# Top_Board.net
KiCad netlist of a schematic drawn in EAGLE
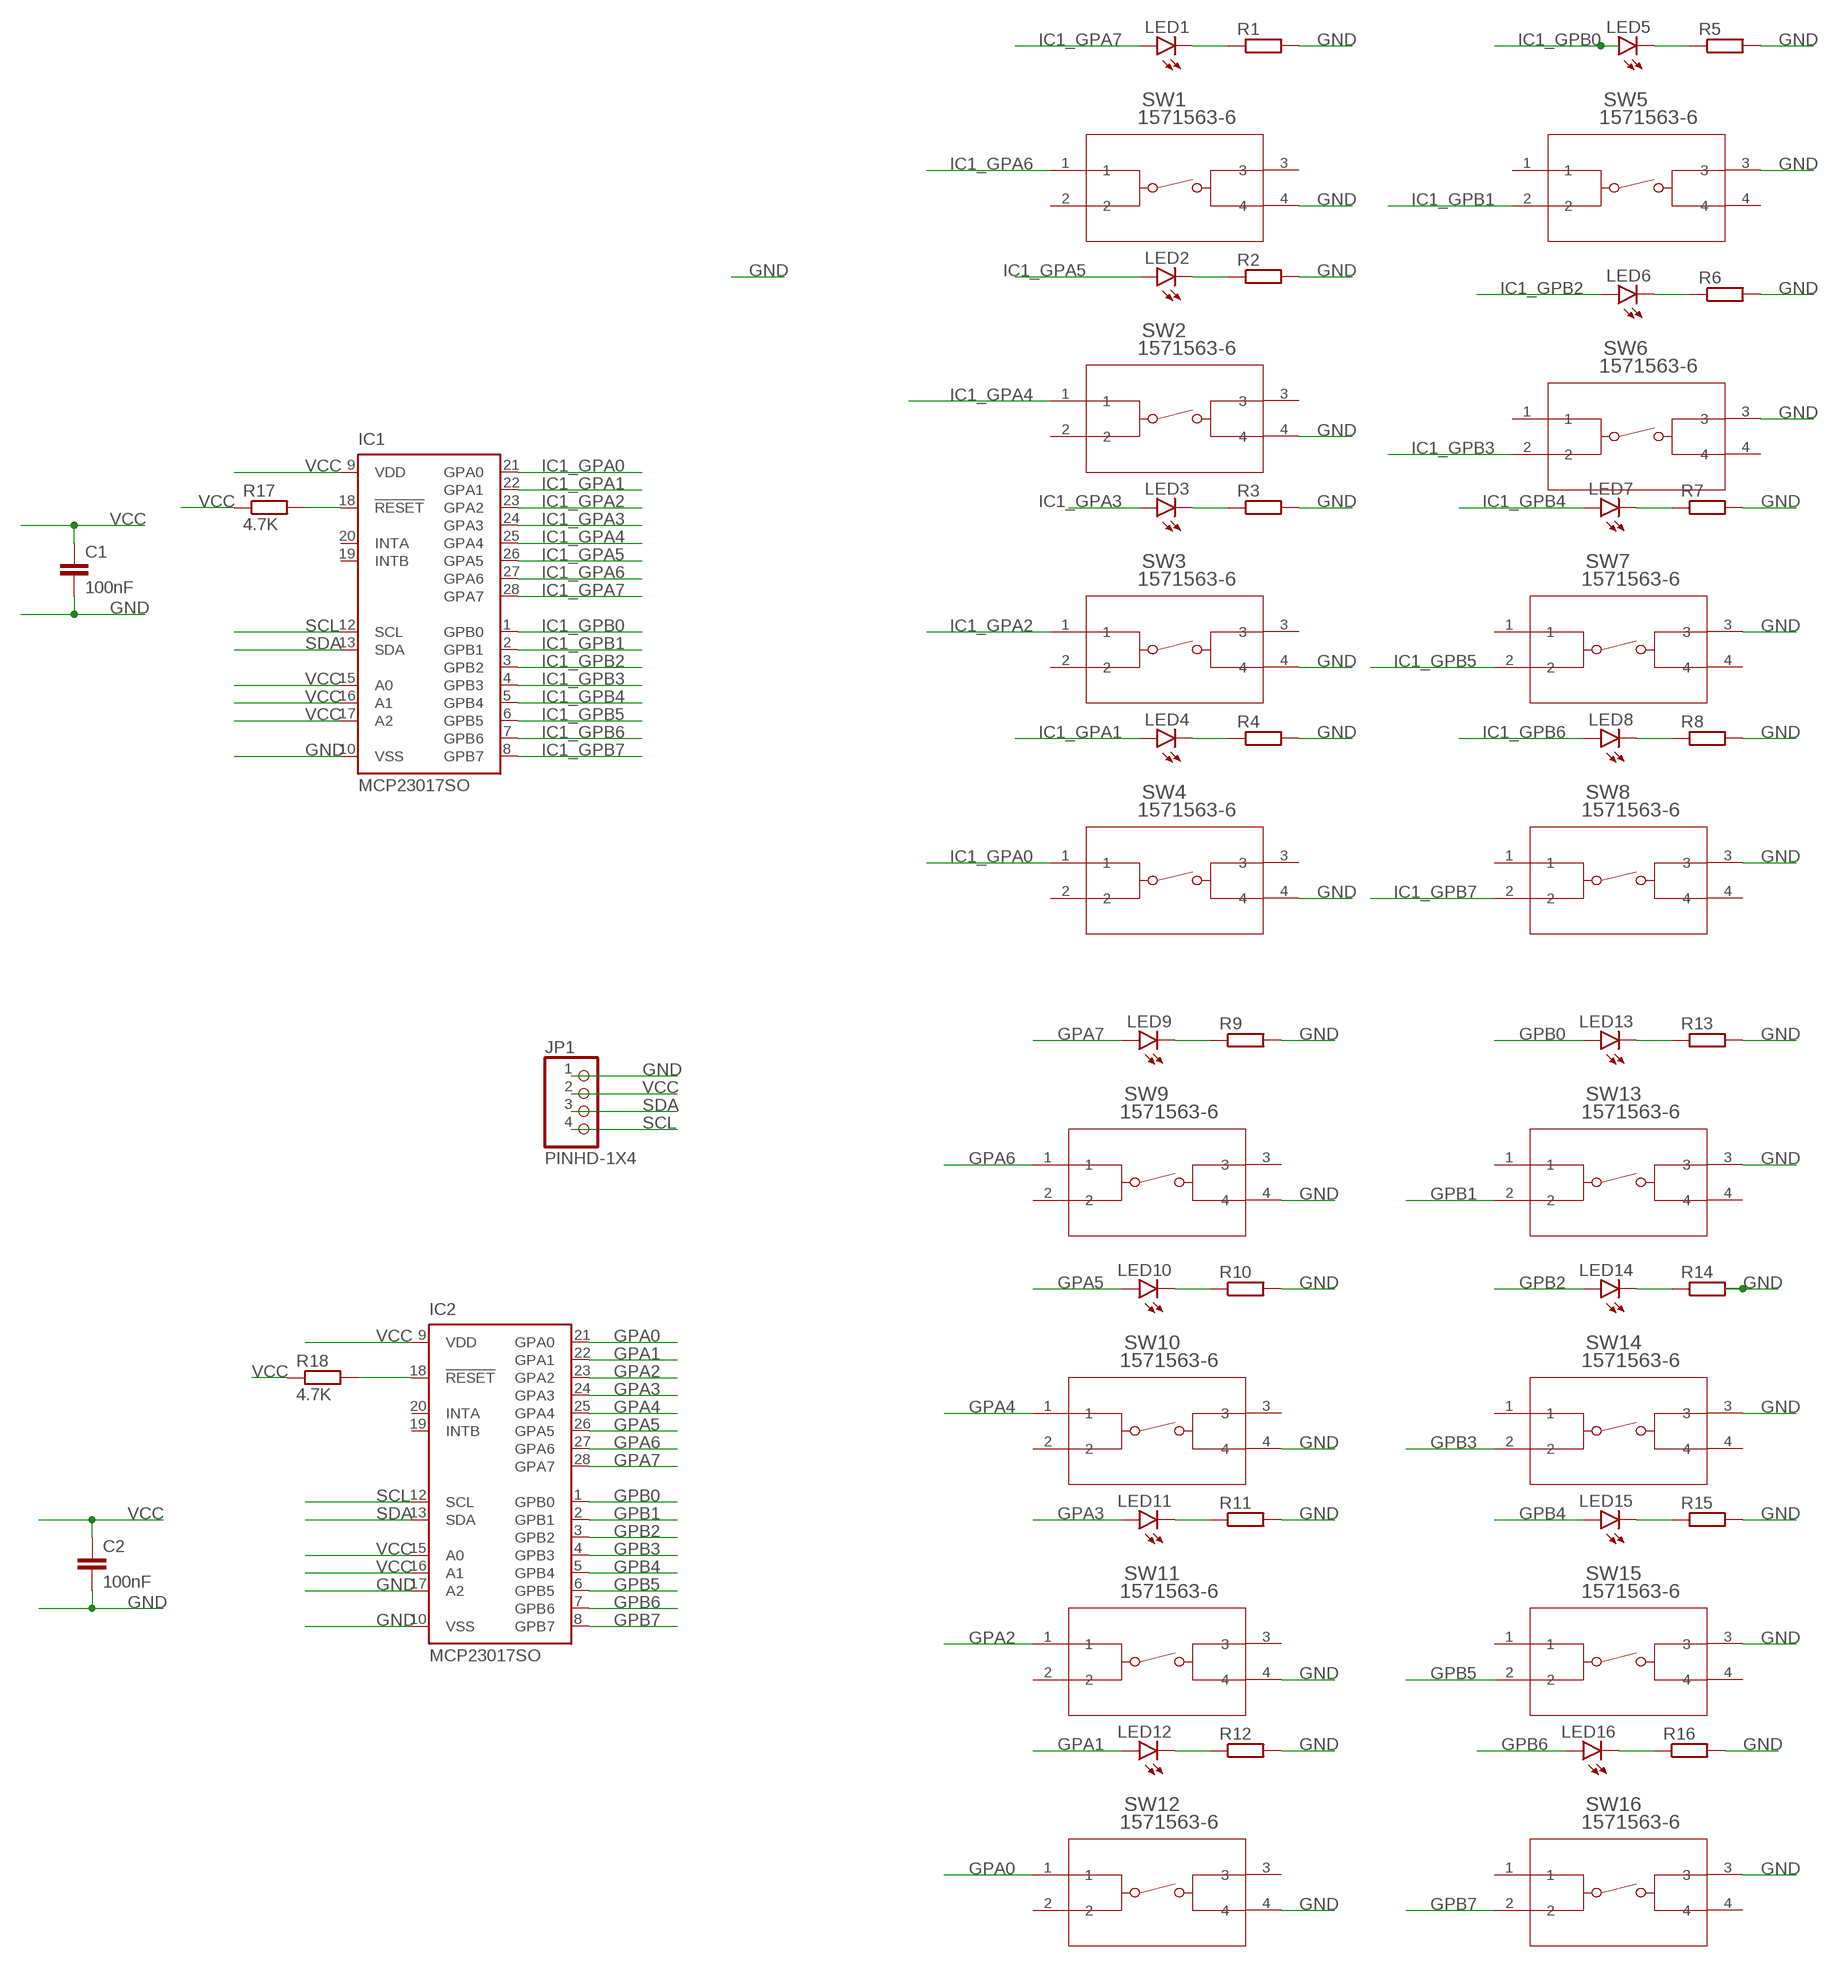
[diagram p0: schematic, sheet 1]

(export (version "E")
  (design (tool "Eeschema 10.0.6"))
  (components
    (comp (ref "C1")
      (value "100nF")
      (footprint "eagle-import:C025-025X050")
      (libsource (lib "eagle-import") (part "C-EU025-025X050"))
    )
    (comp (ref "C2")
      (value "100nF")
      (footprint "eagle-import:C025-025X050")
      (libsource (lib "eagle-import") (part "C-EU025-025X050"))
    )
    (comp (ref "IC1")
      (value "MCP23017SO")
      (footprint "eagle-import:SO28W")
      (fields (field (name "MF") "MICROCHIP") (field (name "MPN") "MCP23017-E/SO"))
      (libsource (lib "eagle-import") (part "MCP23017SO"))
    )
    (comp (ref "IC2")
      (value "MCP23017SO")
      (footprint "eagle-import:SO28W")
      (fields (field (name "MF") "MICROCHIP") (field (name "MPN") "MCP23017-E/SO"))
      (libsource (lib "eagle-import") (part "MCP23017SO"))
    )
    (comp (ref "JP1")
      (value "PINHD-1X4")
      (footprint "eagle-import:1X04")
      (libsource (lib "eagle-import") (part "PINHD-1X4"))
    )
    (comp (ref "LED1")
      (value "LEDCHIP-LED0805")
      (footprint "eagle-import:CHIP-LED0805")
      (libsource (lib "eagle-import") (part "LEDCHIP-LED0805"))
    )
    (comp (ref "LED2")
      (value "LEDCHIP-LED0805")
      (footprint "eagle-import:CHIP-LED0805")
      (libsource (lib "eagle-import") (part "LEDCHIP-LED0805"))
    )
    (comp (ref "LED3")
      (value "LEDCHIP-LED0805")
      (footprint "eagle-import:CHIP-LED0805")
      (libsource (lib "eagle-import") (part "LEDCHIP-LED0805"))
    )
    (comp (ref "LED4")
      (value "LEDCHIP-LED0805")
      (footprint "eagle-import:CHIP-LED0805")
      (libsource (lib "eagle-import") (part "LEDCHIP-LED0805"))
    )
    (comp (ref "LED5")
      (value "LEDCHIP-LED0805")
      (footprint "eagle-import:CHIP-LED0805")
      (libsource (lib "eagle-import") (part "LEDCHIP-LED0805"))
    )
    (comp (ref "LED6")
      (value "LEDCHIP-LED0805")
      (footprint "eagle-import:CHIP-LED0805")
      (libsource (lib "eagle-import") (part "LEDCHIP-LED0805"))
    )
    (comp (ref "LED7")
      (value "LEDCHIP-LED0805")
      (footprint "eagle-import:CHIP-LED0805")
      (libsource (lib "eagle-import") (part "LEDCHIP-LED0805"))
    )
    (comp (ref "LED8")
      (value "LEDCHIP-LED0805")
      (footprint "eagle-import:CHIP-LED0805")
      (libsource (lib "eagle-import") (part "LEDCHIP-LED0805"))
    )
    (comp (ref "LED9")
      (value "LEDCHIP-LED0805")
      (footprint "eagle-import:CHIP-LED0805")
      (libsource (lib "eagle-import") (part "LEDCHIP-LED0805"))
    )
    (comp (ref "LED10")
      (value "LEDCHIP-LED0805")
      (footprint "eagle-import:CHIP-LED0805")
      (libsource (lib "eagle-import") (part "LEDCHIP-LED0805"))
    )
    (comp (ref "LED11")
      (value "LEDCHIP-LED0805")
      (footprint "eagle-import:CHIP-LED0805")
      (libsource (lib "eagle-import") (part "LEDCHIP-LED0805"))
    )
    (comp (ref "LED12")
      (value "LEDCHIP-LED0805")
      (footprint "eagle-import:CHIP-LED0805")
      (libsource (lib "eagle-import") (part "LEDCHIP-LED0805"))
    )
    (comp (ref "LED13")
      (value "LEDCHIP-LED0805")
      (footprint "eagle-import:CHIP-LED0805")
      (libsource (lib "eagle-import") (part "LEDCHIP-LED0805"))
    )
    (comp (ref "LED14")
      (value "LEDCHIP-LED0805")
      (footprint "eagle-import:CHIP-LED0805")
      (libsource (lib "eagle-import") (part "LEDCHIP-LED0805"))
    )
    (comp (ref "LED15")
      (value "LEDCHIP-LED0805")
      (footprint "eagle-import:CHIP-LED0805")
      (libsource (lib "eagle-import") (part "LEDCHIP-LED0805"))
    )
    (comp (ref "LED16")
      (value "LEDCHIP-LED0805")
      (footprint "eagle-import:CHIP-LED0805")
      (libsource (lib "eagle-import") (part "LEDCHIP-LED0805"))
    )
    (comp (ref "R1")
      (value "R-EU_R0805")
      (footprint "eagle-import:R0805")
      (libsource (lib "eagle-import") (part "R-EU_R0805"))
    )
    (comp (ref "R2")
      (value "R-EU_R0805")
      (footprint "eagle-import:R0805")
      (libsource (lib "eagle-import") (part "R-EU_R0805"))
    )
    (comp (ref "R3")
      (value "R-EU_R0805")
      (footprint "eagle-import:R0805")
      (libsource (lib "eagle-import") (part "R-EU_R0805"))
    )
    (comp (ref "R4")
      (value "R-EU_R0805")
      (footprint "eagle-import:R0805")
      (libsource (lib "eagle-import") (part "R-EU_R0805"))
    )
    (comp (ref "R5")
      (value "R-EU_R0805")
      (footprint "eagle-import:R0805")
      (libsource (lib "eagle-import") (part "R-EU_R0805"))
    )
    (comp (ref "R6")
      (value "R-EU_R0805")
      (footprint "eagle-import:R0805")
      (libsource (lib "eagle-import") (part "R-EU_R0805"))
    )
    (comp (ref "R7")
      (value "R-EU_R0805")
      (footprint "eagle-import:R0805")
      (libsource (lib "eagle-import") (part "R-EU_R0805"))
    )
    (comp (ref "R8")
      (value "R-EU_R0805")
      (footprint "eagle-import:R0805")
      (libsource (lib "eagle-import") (part "R-EU_R0805"))
    )
    (comp (ref "R9")
      (value "R-EU_R0805")
      (footprint "eagle-import:R0805")
      (libsource (lib "eagle-import") (part "R-EU_R0805"))
    )
    (comp (ref "R10")
      (value "R-EU_R0805")
      (footprint "eagle-import:R0805")
      (libsource (lib "eagle-import") (part "R-EU_R0805"))
    )
    (comp (ref "R11")
      (value "R-EU_R0805")
      (footprint "eagle-import:R0805")
      (libsource (lib "eagle-import") (part "R-EU_R0805"))
    )
    (comp (ref "R12")
      (value "R-EU_R0805")
      (footprint "eagle-import:R0805")
      (libsource (lib "eagle-import") (part "R-EU_R0805"))
    )
    (comp (ref "R13")
      (value "R-EU_R0805")
      (footprint "eagle-import:R0805")
      (libsource (lib "eagle-import") (part "R-EU_R0805"))
    )
    (comp (ref "R14")
      (value "R-EU_R0805")
      (footprint "eagle-import:R0805")
      (libsource (lib "eagle-import") (part "R-EU_R0805"))
    )
    (comp (ref "R15")
      (value "R-EU_R0805")
      (footprint "eagle-import:R0805")
      (libsource (lib "eagle-import") (part "R-EU_R0805"))
    )
    (comp (ref "R16")
      (value "R-EU_R0805")
      (footprint "eagle-import:R0805")
      (libsource (lib "eagle-import") (part "R-EU_R0805"))
    )
    (comp (ref "R17")
      (value "4.7K")
      (footprint "eagle-import:R0805")
      (libsource (lib "eagle-import") (part "R-EU_R0805"))
    )
    (comp (ref "R18")
      (value "4.7K")
      (footprint "eagle-import:R0805")
      (libsource (lib "eagle-import") (part "R-EU_R0805"))
    )
    (comp (ref "SW1")
      (value "1571563-6")
      (footprint "eagle-import:SW4_1437565-E")
      (fields (field (name "COPYRIGHT") "Copyright (C) 2016 Accelerated Designs. All rights reserved"))
      (libsource (lib "eagle-import") (part "1571563-6"))
    )
    (comp (ref "SW2")
      (value "1571563-6")
      (footprint "eagle-import:SW4_1437565-E")
      (fields (field (name "COPYRIGHT") "Copyright (C) 2016 Accelerated Designs. All rights reserved"))
      (libsource (lib "eagle-import") (part "1571563-6"))
    )
    (comp (ref "SW3")
      (value "1571563-6")
      (footprint "eagle-import:SW4_1437565-E")
      (fields (field (name "COPYRIGHT") "Copyright (C) 2016 Accelerated Designs. All rights reserved"))
      (libsource (lib "eagle-import") (part "1571563-6"))
    )
    (comp (ref "SW4")
      (value "1571563-6")
      (footprint "eagle-import:SW4_1437565-E")
      (fields (field (name "COPYRIGHT") "Copyright (C) 2016 Accelerated Designs. All rights reserved"))
      (libsource (lib "eagle-import") (part "1571563-6"))
    )
    (comp (ref "SW5")
      (value "1571563-6")
      (footprint "eagle-import:SW4_1437565-E")
      (fields (field (name "COPYRIGHT") "Copyright (C) 2016 Accelerated Designs. All rights reserved"))
      (libsource (lib "eagle-import") (part "1571563-6"))
    )
    (comp (ref "SW6")
      (value "1571563-6")
      (footprint "eagle-import:SW4_1437565-E")
      (fields (field (name "COPYRIGHT") "Copyright (C) 2016 Accelerated Designs. All rights reserved"))
      (libsource (lib "eagle-import") (part "1571563-6"))
    )
    (comp (ref "SW7")
      (value "1571563-6")
      (footprint "eagle-import:SW4_1437565-E")
      (fields (field (name "COPYRIGHT") "Copyright (C) 2016 Accelerated Designs. All rights reserved"))
      (libsource (lib "eagle-import") (part "1571563-6"))
    )
    (comp (ref "SW8")
      (value "1571563-6")
      (footprint "eagle-import:SW4_1437565-E")
      (fields (field (name "COPYRIGHT") "Copyright (C) 2016 Accelerated Designs. All rights reserved"))
      (libsource (lib "eagle-import") (part "1571563-6"))
    )
    (comp (ref "SW9")
      (value "1571563-6")
      (footprint "eagle-import:SW4_1437565-E")
      (fields (field (name "COPYRIGHT") "Copyright (C) 2016 Accelerated Designs. All rights reserved"))
      (libsource (lib "eagle-import") (part "1571563-6"))
    )
    (comp (ref "SW10")
      (value "1571563-6")
      (footprint "eagle-import:SW4_1437565-E")
      (fields (field (name "COPYRIGHT") "Copyright (C) 2016 Accelerated Designs. All rights reserved"))
      (libsource (lib "eagle-import") (part "1571563-6"))
    )
    (comp (ref "SW11")
      (value "1571563-6")
      (footprint "eagle-import:SW4_1437565-E")
      (fields (field (name "COPYRIGHT") "Copyright (C) 2016 Accelerated Designs. All rights reserved"))
      (libsource (lib "eagle-import") (part "1571563-6"))
    )
    (comp (ref "SW12")
      (value "1571563-6")
      (footprint "eagle-import:SW4_1437565-E")
      (fields (field (name "COPYRIGHT") "Copyright (C) 2016 Accelerated Designs. All rights reserved"))
      (libsource (lib "eagle-import") (part "1571563-6"))
    )
    (comp (ref "SW13")
      (value "1571563-6")
      (footprint "eagle-import:SW4_1437565-E")
      (fields (field (name "COPYRIGHT") "Copyright (C) 2016 Accelerated Designs. All rights reserved"))
      (libsource (lib "eagle-import") (part "1571563-6"))
    )
    (comp (ref "SW14")
      (value "1571563-6")
      (footprint "eagle-import:SW4_1437565-E")
      (fields (field (name "COPYRIGHT") "Copyright (C) 2016 Accelerated Designs. All rights reserved"))
      (libsource (lib "eagle-import") (part "1571563-6"))
    )
    (comp (ref "SW15")
      (value "1571563-6")
      (footprint "eagle-import:SW4_1437565-E")
      (fields (field (name "COPYRIGHT") "Copyright (C) 2016 Accelerated Designs. All rights reserved"))
      (libsource (lib "eagle-import") (part "1571563-6"))
    )
    (comp (ref "SW16")
      (value "1571563-6")
      (footprint "eagle-import:SW4_1437565-E")
      (fields (field (name "COPYRIGHT") "Copyright (C) 2016 Accelerated Designs. All rights reserved"))
      (libsource (lib "eagle-import") (part "1571563-6"))
    )
  )
  (nets
    (net (code "1") (name "/GND") (class "Default")
      (node (ref "C1") (pin "2") (pinfunction "2_2") (pintype "passive"))
      (node (ref "C2") (pin "2") (pinfunction "2_2") (pintype "passive"))
      (node (ref "IC1") (pin "10") (pinfunction "VSS_10") (pintype "power_in"))
      (node (ref "IC2") (pin "10") (pinfunction "VSS_10") (pintype "power_in"))
      (node (ref "IC2") (pin "17") (pinfunction "A2_17") (pintype "input"))
      (node (ref "JP1") (pin "1") (pinfunction "1_1") (pintype "passive"))
      (node (ref "R1") (pin "2") (pinfunction "2_2") (pintype "passive"))
      (node (ref "R10") (pin "2") (pinfunction "2_2") (pintype "passive"))
      (node (ref "R11") (pin "2") (pinfunction "2_2") (pintype "passive"))
      (node (ref "R12") (pin "2") (pinfunction "2_2") (pintype "passive"))
      (node (ref "R13") (pin "2") (pinfunction "2_2") (pintype "passive"))
      (node (ref "R14") (pin "2") (pinfunction "2_2") (pintype "passive"))
      (node (ref "R15") (pin "2") (pinfunction "2_2") (pintype "passive"))
      (node (ref "R16") (pin "2") (pinfunction "2_2") (pintype "passive"))
      (node (ref "R2") (pin "2") (pinfunction "2_2") (pintype "passive"))
      (node (ref "R3") (pin "2") (pinfunction "2_2") (pintype "passive"))
      (node (ref "R4") (pin "2") (pinfunction "2_2") (pintype "passive"))
      (node (ref "R5") (pin "2") (pinfunction "2_2") (pintype "passive"))
      (node (ref "R6") (pin "2") (pinfunction "2_2") (pintype "passive"))
      (node (ref "R7") (pin "2") (pinfunction "2_2") (pintype "passive"))
      (node (ref "R8") (pin "2") (pinfunction "2_2") (pintype "passive"))
      (node (ref "R9") (pin "2") (pinfunction "2_2") (pintype "passive"))
      (node (ref "SW1") (pin "4") (pinfunction "4_4") (pintype "passive"))
      (node (ref "SW10") (pin "4") (pinfunction "4_4") (pintype "passive"))
      (node (ref "SW11") (pin "4") (pinfunction "4_4") (pintype "passive"))
      (node (ref "SW12") (pin "4") (pinfunction "4_4") (pintype "passive"))
      (node (ref "SW13") (pin "3") (pinfunction "3_3") (pintype "passive"))
      (node (ref "SW14") (pin "3") (pinfunction "3_3") (pintype "passive"))
      (node (ref "SW15") (pin "3") (pinfunction "3_3") (pintype "passive"))
      (node (ref "SW16") (pin "3") (pinfunction "3_3") (pintype "passive"))
      (node (ref "SW2") (pin "4") (pinfunction "4_4") (pintype "passive"))
      (node (ref "SW3") (pin "4") (pinfunction "4_4") (pintype "passive"))
      (node (ref "SW4") (pin "4") (pinfunction "4_4") (pintype "passive"))
      (node (ref "SW5") (pin "3") (pinfunction "3_3") (pintype "passive"))
      (node (ref "SW6") (pin "3") (pinfunction "3_3") (pintype "passive"))
      (node (ref "SW7") (pin "3") (pinfunction "3_3") (pintype "passive"))
      (node (ref "SW8") (pin "3") (pinfunction "3_3") (pintype "passive"))
      (node (ref "SW9") (pin "4") (pinfunction "4_4") (pintype "passive"))
    )
    (net (code "2") (name "/GPA0") (class "Default")
      (node (ref "IC2") (pin "21") (pinfunction "GPA0_21") (pintype "bidirectional"))
      (node (ref "SW12") (pin "1") (pinfunction "1_1") (pintype "passive"))
    )
    (net (code "3") (name "/GPA1") (class "Default")
      (node (ref "IC2") (pin "22") (pinfunction "GPA1_22") (pintype "bidirectional"))
      (node (ref "LED12") (pin "A") (pinfunction "A_A") (pintype "passive"))
    )
    (net (code "4") (name "/GPA2") (class "Default")
      (node (ref "IC2") (pin "23") (pinfunction "GPA2_23") (pintype "bidirectional"))
      (node (ref "SW11") (pin "1") (pinfunction "1_1") (pintype "passive"))
    )
    (net (code "5") (name "/GPA3") (class "Default")
      (node (ref "IC2") (pin "24") (pinfunction "GPA3_24") (pintype "bidirectional"))
      (node (ref "LED11") (pin "A") (pinfunction "A_A") (pintype "passive"))
    )
    (net (code "6") (name "/GPA4") (class "Default")
      (node (ref "IC2") (pin "25") (pinfunction "GPA4_25") (pintype "bidirectional"))
      (node (ref "SW10") (pin "1") (pinfunction "1_1") (pintype "passive"))
    )
    (net (code "7") (name "/GPA5") (class "Default")
      (node (ref "IC2") (pin "26") (pinfunction "GPA5_26") (pintype "bidirectional"))
      (node (ref "LED10") (pin "A") (pinfunction "A_A") (pintype "passive"))
    )
    (net (code "8") (name "/GPA6") (class "Default")
      (node (ref "IC2") (pin "27") (pinfunction "GPA6_27") (pintype "bidirectional"))
      (node (ref "SW9") (pin "1") (pinfunction "1_1") (pintype "passive"))
    )
    (net (code "9") (name "/GPA7") (class "Default")
      (node (ref "IC2") (pin "28") (pinfunction "GPA7_28") (pintype "bidirectional"))
      (node (ref "LED9") (pin "A") (pinfunction "A_A") (pintype "passive"))
    )
    (net (code "10") (name "/GPB0") (class "Default")
      (node (ref "IC2") (pin "1") (pinfunction "GPB0_1") (pintype "bidirectional"))
      (node (ref "LED13") (pin "A") (pinfunction "A_A") (pintype "passive"))
    )
    (net (code "11") (name "/GPB1") (class "Default")
      (node (ref "IC2") (pin "2") (pinfunction "GPB1_2") (pintype "bidirectional"))
      (node (ref "SW13") (pin "2") (pinfunction "2_2") (pintype "passive"))
    )
    (net (code "12") (name "/GPB2") (class "Default")
      (node (ref "IC2") (pin "3") (pinfunction "GPB2_3") (pintype "bidirectional"))
      (node (ref "LED14") (pin "A") (pinfunction "A_A") (pintype "passive"))
    )
    (net (code "13") (name "/GPB3") (class "Default")
      (node (ref "IC2") (pin "4") (pinfunction "GPB3_4") (pintype "bidirectional"))
      (node (ref "SW14") (pin "2") (pinfunction "2_2") (pintype "passive"))
    )
    (net (code "14") (name "/GPB4") (class "Default")
      (node (ref "IC2") (pin "5") (pinfunction "GPB4_5") (pintype "bidirectional"))
      (node (ref "LED15") (pin "A") (pinfunction "A_A") (pintype "passive"))
    )
    (net (code "15") (name "/GPB5") (class "Default")
      (node (ref "IC2") (pin "6") (pinfunction "GPB5_6") (pintype "bidirectional"))
      (node (ref "SW15") (pin "2") (pinfunction "2_2") (pintype "passive"))
    )
    (net (code "16") (name "/GPB6") (class "Default")
      (node (ref "IC2") (pin "7") (pinfunction "GPB6_7") (pintype "bidirectional"))
      (node (ref "LED16") (pin "A") (pinfunction "A_A") (pintype "passive"))
    )
    (net (code "17") (name "/GPB7") (class "Default")
      (node (ref "IC2") (pin "8") (pinfunction "GPB7_8") (pintype "bidirectional"))
      (node (ref "SW16") (pin "2") (pinfunction "2_2") (pintype "passive"))
    )
    (net (code "18") (name "/IC1_GPA0") (class "Default")
      (node (ref "IC1") (pin "21") (pinfunction "GPA0_21") (pintype "bidirectional"))
      (node (ref "SW4") (pin "1") (pinfunction "1_1") (pintype "passive"))
    )
    (net (code "19") (name "/IC1_GPA1") (class "Default")
      (node (ref "IC1") (pin "22") (pinfunction "GPA1_22") (pintype "bidirectional"))
      (node (ref "LED4") (pin "A") (pinfunction "A_A") (pintype "passive"))
    )
    (net (code "20") (name "/IC1_GPA2") (class "Default")
      (node (ref "IC1") (pin "23") (pinfunction "GPA2_23") (pintype "bidirectional"))
      (node (ref "SW3") (pin "1") (pinfunction "1_1") (pintype "passive"))
    )
    (net (code "21") (name "/IC1_GPA3") (class "Default")
      (node (ref "IC1") (pin "24") (pinfunction "GPA3_24") (pintype "bidirectional"))
      (node (ref "LED3") (pin "A") (pinfunction "A_A") (pintype "passive"))
    )
    (net (code "22") (name "/IC1_GPA4") (class "Default")
      (node (ref "IC1") (pin "25") (pinfunction "GPA4_25") (pintype "bidirectional"))
      (node (ref "SW2") (pin "1") (pinfunction "1_1") (pintype "passive"))
    )
    (net (code "23") (name "/IC1_GPA5") (class "Default")
      (node (ref "IC1") (pin "26") (pinfunction "GPA5_26") (pintype "bidirectional"))
      (node (ref "LED2") (pin "A") (pinfunction "A_A") (pintype "passive"))
    )
    (net (code "24") (name "/IC1_GPA6") (class "Default")
      (node (ref "IC1") (pin "27") (pinfunction "GPA6_27") (pintype "bidirectional"))
      (node (ref "SW1") (pin "1") (pinfunction "1_1") (pintype "passive"))
    )
    (net (code "25") (name "/IC1_GPA7") (class "Default")
      (node (ref "IC1") (pin "28") (pinfunction "GPA7_28") (pintype "bidirectional"))
      (node (ref "LED1") (pin "A") (pinfunction "A_A") (pintype "passive"))
    )
    (net (code "26") (name "/IC1_GPB0") (class "Default")
      (node (ref "IC1") (pin "1") (pinfunction "GPB0_1") (pintype "bidirectional"))
      (node (ref "LED5") (pin "A") (pinfunction "A_A") (pintype "passive"))
    )
    (net (code "27") (name "/IC1_GPB1") (class "Default")
      (node (ref "IC1") (pin "2") (pinfunction "GPB1_2") (pintype "bidirectional"))
      (node (ref "SW5") (pin "2") (pinfunction "2_2") (pintype "passive"))
    )
    (net (code "28") (name "/IC1_GPB2") (class "Default")
      (node (ref "IC1") (pin "3") (pinfunction "GPB2_3") (pintype "bidirectional"))
      (node (ref "LED6") (pin "A") (pinfunction "A_A") (pintype "passive"))
    )
    (net (code "29") (name "/IC1_GPB3") (class "Default")
      (node (ref "IC1") (pin "4") (pinfunction "GPB3_4") (pintype "bidirectional"))
      (node (ref "SW6") (pin "2") (pinfunction "2_2") (pintype "passive"))
    )
    (net (code "30") (name "/IC1_GPB4") (class "Default")
      (node (ref "IC1") (pin "5") (pinfunction "GPB4_5") (pintype "bidirectional"))
      (node (ref "LED7") (pin "A") (pinfunction "A_A") (pintype "passive"))
    )
    (net (code "31") (name "/IC1_GPB5") (class "Default")
      (node (ref "IC1") (pin "6") (pinfunction "GPB5_6") (pintype "bidirectional"))
      (node (ref "SW7") (pin "2") (pinfunction "2_2") (pintype "passive"))
    )
    (net (code "32") (name "/IC1_GPB6") (class "Default")
      (node (ref "IC1") (pin "7") (pinfunction "GPB6_7") (pintype "bidirectional"))
      (node (ref "LED8") (pin "A") (pinfunction "A_A") (pintype "passive"))
    )
    (net (code "33") (name "/IC1_GPB7") (class "Default")
      (node (ref "IC1") (pin "8") (pinfunction "GPB7_8") (pintype "bidirectional"))
      (node (ref "SW8") (pin "2") (pinfunction "2_2") (pintype "passive"))
    )
    (net (code "34") (name "/SCL") (class "Default")
      (node (ref "IC1") (pin "12") (pinfunction "SCL_12") (pintype "input"))
      (node (ref "IC2") (pin "12") (pinfunction "SCL_12") (pintype "input"))
      (node (ref "JP1") (pin "4") (pinfunction "4_4") (pintype "passive"))
    )
    (net (code "35") (name "/SDA") (class "Default")
      (node (ref "IC1") (pin "13") (pinfunction "SDA_13") (pintype "bidirectional"))
      (node (ref "IC2") (pin "13") (pinfunction "SDA_13") (pintype "bidirectional"))
      (node (ref "JP1") (pin "3") (pinfunction "3_3") (pintype "passive"))
    )
    (net (code "36") (name "/VCC") (class "Default")
      (node (ref "C1") (pin "1") (pinfunction "1_1") (pintype "passive"))
      (node (ref "C2") (pin "1") (pinfunction "1_1") (pintype "passive"))
      (node (ref "IC1") (pin "15") (pinfunction "A0_15") (pintype "input"))
      (node (ref "IC1") (pin "16") (pinfunction "A1_16") (pintype "input"))
      (node (ref "IC1") (pin "17") (pinfunction "A2_17") (pintype "input"))
      (node (ref "IC1") (pin "9") (pinfunction "VDD_9") (pintype "power_in"))
      (node (ref "IC2") (pin "15") (pinfunction "A0_15") (pintype "input"))
      (node (ref "IC2") (pin "16") (pinfunction "A1_16") (pintype "input"))
      (node (ref "IC2") (pin "9") (pinfunction "VDD_9") (pintype "power_in"))
      (node (ref "JP1") (pin "2") (pinfunction "2_2") (pintype "passive"))
      (node (ref "R17") (pin "1") (pinfunction "1_1") (pintype "passive"))
      (node (ref "R18") (pin "1") (pinfunction "1_1") (pintype "passive"))
    )
    (net (code "37") (name "Net-(IC1-~{RESET})") (class "Default")
      (node (ref "IC1") (pin "18") (pinfunction "~{RESET}_18") (pintype "input"))
      (node (ref "R17") (pin "2") (pinfunction "2_2") (pintype "passive"))
    )
    (net (code "38") (name "Net-(IC2-~{RESET})") (class "Default")
      (node (ref "IC2") (pin "18") (pinfunction "~{RESET}_18") (pintype "input"))
      (node (ref "R18") (pin "2") (pinfunction "2_2") (pintype "passive"))
    )
    (net (code "39") (name "Net-(LED1-PadC)") (class "Default")
      (node (ref "LED1") (pin "C") (pinfunction "C_C") (pintype "passive"))
      (node (ref "R1") (pin "1") (pinfunction "1_1") (pintype "passive"))
    )
    (net (code "40") (name "Net-(LED2-PadC)") (class "Default")
      (node (ref "LED2") (pin "C") (pinfunction "C_C") (pintype "passive"))
      (node (ref "R2") (pin "1") (pinfunction "1_1") (pintype "passive"))
    )
    (net (code "41") (name "Net-(LED3-PadC)") (class "Default")
      (node (ref "LED3") (pin "C") (pinfunction "C_C") (pintype "passive"))
      (node (ref "R3") (pin "1") (pinfunction "1_1") (pintype "passive"))
    )
    (net (code "42") (name "Net-(LED4-PadC)") (class "Default")
      (node (ref "LED4") (pin "C") (pinfunction "C_C") (pintype "passive"))
      (node (ref "R4") (pin "1") (pinfunction "1_1") (pintype "passive"))
    )
    (net (code "43") (name "Net-(LED5-PadC)") (class "Default")
      (node (ref "LED5") (pin "C") (pinfunction "C_C") (pintype "passive"))
      (node (ref "R5") (pin "1") (pinfunction "1_1") (pintype "passive"))
    )
    (net (code "44") (name "Net-(LED6-PadC)") (class "Default")
      (node (ref "LED6") (pin "C") (pinfunction "C_C") (pintype "passive"))
      (node (ref "R6") (pin "1") (pinfunction "1_1") (pintype "passive"))
    )
    (net (code "45") (name "Net-(LED7-PadC)") (class "Default")
      (node (ref "LED7") (pin "C") (pinfunction "C_C") (pintype "passive"))
      (node (ref "R7") (pin "1") (pinfunction "1_1") (pintype "passive"))
    )
    (net (code "46") (name "Net-(LED8-PadC)") (class "Default")
      (node (ref "LED8") (pin "C") (pinfunction "C_C") (pintype "passive"))
      (node (ref "R8") (pin "1") (pinfunction "1_1") (pintype "passive"))
    )
    (net (code "47") (name "Net-(LED9-PadC)") (class "Default")
      (node (ref "LED9") (pin "C") (pinfunction "C_C") (pintype "passive"))
      (node (ref "R9") (pin "1") (pinfunction "1_1") (pintype "passive"))
    )
    (net (code "48") (name "Net-(LED10-PadC)") (class "Default")
      (node (ref "LED10") (pin "C") (pinfunction "C_C") (pintype "passive"))
      (node (ref "R10") (pin "1") (pinfunction "1_1") (pintype "passive"))
    )
    (net (code "49") (name "Net-(LED11-PadC)") (class "Default")
      (node (ref "LED11") (pin "C") (pinfunction "C_C") (pintype "passive"))
      (node (ref "R11") (pin "1") (pinfunction "1_1") (pintype "passive"))
    )
    (net (code "50") (name "Net-(LED12-PadC)") (class "Default")
      (node (ref "LED12") (pin "C") (pinfunction "C_C") (pintype "passive"))
      (node (ref "R12") (pin "1") (pinfunction "1_1") (pintype "passive"))
    )
    (net (code "51") (name "Net-(LED13-PadC)") (class "Default")
      (node (ref "LED13") (pin "C") (pinfunction "C_C") (pintype "passive"))
      (node (ref "R13") (pin "1") (pinfunction "1_1") (pintype "passive"))
    )
    (net (code "52") (name "Net-(LED14-PadC)") (class "Default")
      (node (ref "LED14") (pin "C") (pinfunction "C_C") (pintype "passive"))
      (node (ref "R14") (pin "1") (pinfunction "1_1") (pintype "passive"))
    )
    (net (code "53") (name "Net-(LED15-PadC)") (class "Default")
      (node (ref "LED15") (pin "C") (pinfunction "C_C") (pintype "passive"))
      (node (ref "R15") (pin "1") (pinfunction "1_1") (pintype "passive"))
    )
    (net (code "54") (name "Net-(LED16-PadC)") (class "Default")
      (node (ref "LED16") (pin "C") (pinfunction "C_C") (pintype "passive"))
      (node (ref "R16") (pin "1") (pinfunction "1_1") (pintype "passive"))
    )
    (net (code "55") (name "unconnected-(IC1-INTA-Pad20)") (class "Default")
      (node (ref "IC1") (pin "20") (pinfunction "INTA_20") (pintype "output"))
    )
    (net (code "56") (name "unconnected-(IC1-INTB-Pad19)") (class "Default")
      (node (ref "IC1") (pin "19") (pinfunction "INTB_19") (pintype "output"))
    )
    (net (code "57") (name "unconnected-(IC2-INTA-Pad20)") (class "Default")
      (node (ref "IC2") (pin "20") (pinfunction "INTA_20") (pintype "output"))
    )
    (net (code "58") (name "unconnected-(IC2-INTB-Pad19)") (class "Default")
      (node (ref "IC2") (pin "19") (pinfunction "INTB_19") (pintype "output"))
    )
    (net (code "59") (name "unconnected-(SW1-Pad2)") (class "Default")
      (node (ref "SW1") (pin "2") (pinfunction "2_2") (pintype "passive"))
    )
    (net (code "60") (name "unconnected-(SW1-Pad3)") (class "Default")
      (node (ref "SW1") (pin "3") (pinfunction "3_3") (pintype "passive"))
    )
    (net (code "61") (name "unconnected-(SW2-Pad2)") (class "Default")
      (node (ref "SW2") (pin "2") (pinfunction "2_2") (pintype "passive"))
    )
    (net (code "62") (name "unconnected-(SW2-Pad3)") (class "Default")
      (node (ref "SW2") (pin "3") (pinfunction "3_3") (pintype "passive"))
    )
    (net (code "63") (name "unconnected-(SW3-Pad2)") (class "Default")
      (node (ref "SW3") (pin "2") (pinfunction "2_2") (pintype "passive"))
    )
    (net (code "64") (name "unconnected-(SW3-Pad3)") (class "Default")
      (node (ref "SW3") (pin "3") (pinfunction "3_3") (pintype "passive"))
    )
    (net (code "65") (name "unconnected-(SW4-Pad2)") (class "Default")
      (node (ref "SW4") (pin "2") (pinfunction "2_2") (pintype "passive"))
    )
    (net (code "66") (name "unconnected-(SW4-Pad3)") (class "Default")
      (node (ref "SW4") (pin "3") (pinfunction "3_3") (pintype "passive"))
    )
    (net (code "67") (name "unconnected-(SW5-Pad1)") (class "Default")
      (node (ref "SW5") (pin "1") (pinfunction "1_1") (pintype "passive"))
    )
    (net (code "68") (name "unconnected-(SW5-Pad4)") (class "Default")
      (node (ref "SW5") (pin "4") (pinfunction "4_4") (pintype "passive"))
    )
    (net (code "69") (name "unconnected-(SW6-Pad1)") (class "Default")
      (node (ref "SW6") (pin "1") (pinfunction "1_1") (pintype "passive"))
    )
    (net (code "70") (name "unconnected-(SW6-Pad4)") (class "Default")
      (node (ref "SW6") (pin "4") (pinfunction "4_4") (pintype "passive"))
    )
    (net (code "71") (name "unconnected-(SW7-Pad1)") (class "Default")
      (node (ref "SW7") (pin "1") (pinfunction "1_1") (pintype "passive"))
    )
    (net (code "72") (name "unconnected-(SW7-Pad4)") (class "Default")
      (node (ref "SW7") (pin "4") (pinfunction "4_4") (pintype "passive"))
    )
    (net (code "73") (name "unconnected-(SW8-Pad1)") (class "Default")
      (node (ref "SW8") (pin "1") (pinfunction "1_1") (pintype "passive"))
    )
    (net (code "74") (name "unconnected-(SW8-Pad4)") (class "Default")
      (node (ref "SW8") (pin "4") (pinfunction "4_4") (pintype "passive"))
    )
    (net (code "75") (name "unconnected-(SW9-Pad2)") (class "Default")
      (node (ref "SW9") (pin "2") (pinfunction "2_2") (pintype "passive"))
    )
    (net (code "76") (name "unconnected-(SW9-Pad3)") (class "Default")
      (node (ref "SW9") (pin "3") (pinfunction "3_3") (pintype "passive"))
    )
    (net (code "77") (name "unconnected-(SW10-Pad2)") (class "Default")
      (node (ref "SW10") (pin "2") (pinfunction "2_2") (pintype "passive"))
    )
    (net (code "78") (name "unconnected-(SW10-Pad3)") (class "Default")
      (node (ref "SW10") (pin "3") (pinfunction "3_3") (pintype "passive"))
    )
    (net (code "79") (name "unconnected-(SW11-Pad2)") (class "Default")
      (node (ref "SW11") (pin "2") (pinfunction "2_2") (pintype "passive"))
    )
    (net (code "80") (name "unconnected-(SW11-Pad3)") (class "Default")
      (node (ref "SW11") (pin "3") (pinfunction "3_3") (pintype "passive"))
    )
    (net (code "81") (name "unconnected-(SW12-Pad2)") (class "Default")
      (node (ref "SW12") (pin "2") (pinfunction "2_2") (pintype "passive"))
    )
    (net (code "82") (name "unconnected-(SW12-Pad3)") (class "Default")
      (node (ref "SW12") (pin "3") (pinfunction "3_3") (pintype "passive"))
    )
    (net (code "83") (name "unconnected-(SW13-Pad1)") (class "Default")
      (node (ref "SW13") (pin "1") (pinfunction "1_1") (pintype "passive"))
    )
    (net (code "84") (name "unconnected-(SW13-Pad4)") (class "Default")
      (node (ref "SW13") (pin "4") (pinfunction "4_4") (pintype "passive"))
    )
    (net (code "85") (name "unconnected-(SW14-Pad1)") (class "Default")
      (node (ref "SW14") (pin "1") (pinfunction "1_1") (pintype "passive"))
    )
    (net (code "86") (name "unconnected-(SW14-Pad4)") (class "Default")
      (node (ref "SW14") (pin "4") (pinfunction "4_4") (pintype "passive"))
    )
    (net (code "87") (name "unconnected-(SW15-Pad1)") (class "Default")
      (node (ref "SW15") (pin "1") (pinfunction "1_1") (pintype "passive"))
    )
    (net (code "88") (name "unconnected-(SW15-Pad4)") (class "Default")
      (node (ref "SW15") (pin "4") (pinfunction "4_4") (pintype "passive"))
    )
    (net (code "89") (name "unconnected-(SW16-Pad1)") (class "Default")
      (node (ref "SW16") (pin "1") (pinfunction "1_1") (pintype "passive"))
    )
    (net (code "90") (name "unconnected-(SW16-Pad4)") (class "Default")
      (node (ref "SW16") (pin "4") (pinfunction "4_4") (pintype "passive"))
    )
  )
)
